# QCLogic_Rev_A_Sht3_GPS.net
KiCad netlist of a schematic drawn in Altium Designer
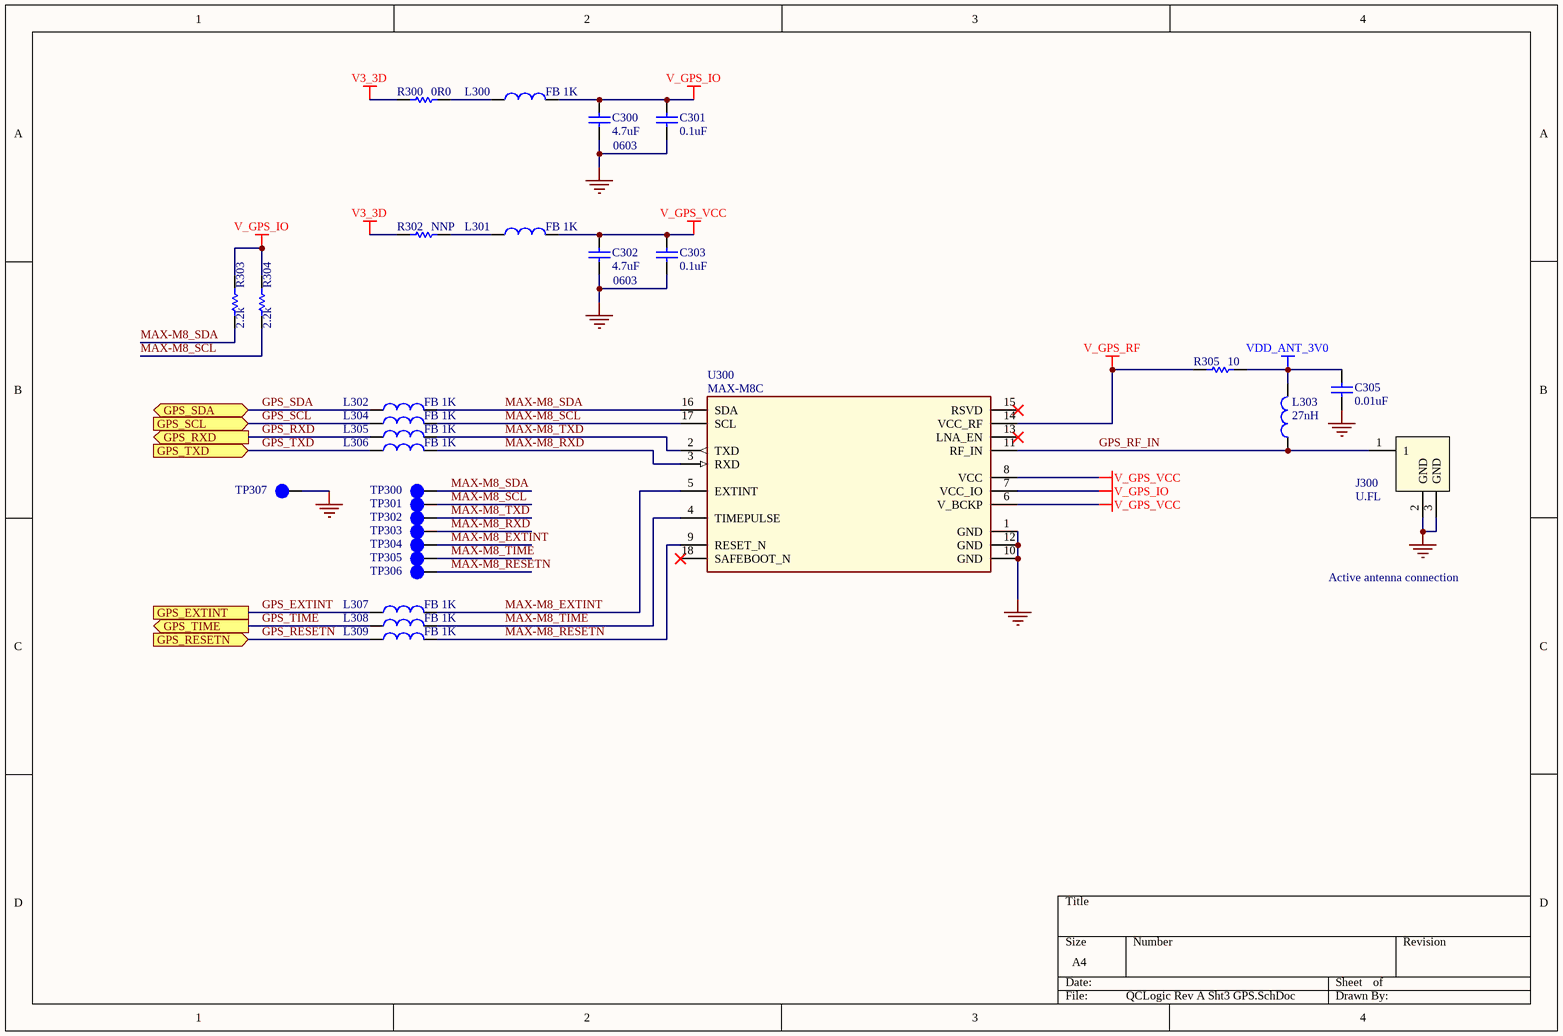
[diagram p0: QCLogic Rev A Sht3 GPS.SchDoc]

(export (version "E")
  (design (tool "Eeschema 10.0.6"))
  (components
    (comp (ref "C300")
      (value "4.7uF")
      (footprint "SMD CAP 0603")
      (description "CAP CER 4.7UF 16V X7S 0603")
      (fields
        (field (name "2. MANUFACTURER PART NUMBER") "GRM188C71C475KE21D")
        (field (name "4. PACKAGE") "0603")
      )
      (libsource (lib "SBCLib") (part "CAP MLCC SMD"))
    )
    (comp (ref "C301")
      (value "0.1uF")
      (footprint "SMD CAP 0402")
      (description "CAP CER 0.1UF 25V X7R 0402")
      (fields (field (name "2. MANUFACTURER PART NUMBER") "CC0402KRX7R8BB104"))
      (libsource (lib "SBCLib") (part "CAP MLCC SMD"))
    )
    (comp (ref "C302")
      (value "4.7uF")
      (footprint "SMD CAP 0603")
      (description "CAP CER 4.7UF 16V X7S 0603")
      (fields
        (field (name "2. MANUFACTURER PART NUMBER") "GRM188C71C475KE21D")
        (field (name "4. PACKAGE") "0603")
      )
      (libsource (lib "SBCLib") (part "CAP MLCC SMD"))
    )
    (comp (ref "C303")
      (value "0.1uF")
      (footprint "SMD CAP 0402")
      (description "CAP CER 0.1UF 25V X7R 0402")
      (fields (field (name "2. MANUFACTURER PART NUMBER") "CC0402KRX7R8BB104"))
      (libsource (lib "SBCLib") (part "CAP MLCC SMD"))
    )
    (comp (ref "C305")
      (value "0.01uF")
      (footprint "SMD CAP 0402")
      (description "CAP CER 10000PF 16V X7R 0402")
      (fields (field (name "2. MANUFACTURER PART NUMBER") "0402B103K160CT"))
      (libsource (lib "SBCLib") (part "CAP MLCC SMD"))
    )
    (comp (ref "J300")
      (value "U.FL")
      (footprint "U.FL")
      (description "CONN UMCC MICRO-COAX RECEPTACLE, GEN")
      (fields (field (name "2. MANUFACTURER PART NUMBER") "2337019-1"))
      (libsource (lib "SBCLib") (part "CONN UMCC MICRO-COAX RECEPTACLE, GEN"))
    )
    (comp (ref "L300")
      (value "FB 1K")
      (footprint "SMD RES 0402")
      (description "FERRITE BEAD 1 KOHM 0402 1LN")
      (fields (field (name "2. MANUFACTURER PART NUMBER") "BLM15HD102SN1D"))
      (libsource (lib "SBCLib") (part "INDUCTOR"))
    )
    (comp (ref "L301")
      (value "FB 1K")
      (footprint "SMD RES 0402")
      (description "FERRITE BEAD 1 KOHM 0402 1LN")
      (fields (field (name "2. MANUFACTURER PART NUMBER") "BLM15HD102SN1D"))
      (libsource (lib "SBCLib") (part "INDUCTOR"))
    )
    (comp (ref "L302")
      (value "FB 1K")
      (footprint "SMD RES 0402")
      (description "FERRITE BEAD 1 KOHM 0402 1LN")
      (fields (field (name "2. MANUFACTURER PART NUMBER") "BLM15HD102SN1D"))
      (libsource (lib "SBCLib") (part "INDUCTOR"))
    )
    (comp (ref "L303")
      (value "27nH")
      (footprint "SMD RES 0402")
      (description "IND 27NH 350MA 460 MOHM")
      (fields (field (name "2. MANUFACTURER PART NUMBER") "LQG15HS27NJ02D"))
      (libsource (lib "SBCLib") (part "INDUCTOR"))
    )
    (comp (ref "L304")
      (value "FB 1K")
      (footprint "SMD RES 0402")
      (description "FERRITE BEAD 1 KOHM 0402 1LN")
      (fields (field (name "2. MANUFACTURER PART NUMBER") "BLM15HD102SN1D"))
      (libsource (lib "SBCLib") (part "INDUCTOR"))
    )
    (comp (ref "L305")
      (value "FB 1K")
      (footprint "SMD RES 0402")
      (description "FERRITE BEAD 1 KOHM 0402 1LN")
      (fields (field (name "2. MANUFACTURER PART NUMBER") "BLM15HD102SN1D"))
      (libsource (lib "SBCLib") (part "INDUCTOR"))
    )
    (comp (ref "L306")
      (value "FB 1K")
      (footprint "SMD RES 0402")
      (description "FERRITE BEAD 1 KOHM 0402 1LN")
      (fields (field (name "2. MANUFACTURER PART NUMBER") "BLM15HD102SN1D"))
      (libsource (lib "SBCLib") (part "INDUCTOR"))
    )
    (comp (ref "L307")
      (value "FB 1K")
      (footprint "SMD RES 0402")
      (description "FERRITE BEAD 1 KOHM 0402 1LN")
      (fields (field (name "2. MANUFACTURER PART NUMBER") "BLM15HD102SN1D"))
      (libsource (lib "SBCLib") (part "INDUCTOR"))
    )
    (comp (ref "L308")
      (value "FB 1K")
      (footprint "SMD RES 0402")
      (description "FERRITE BEAD 1 KOHM 0402 1LN")
      (fields (field (name "2. MANUFACTURER PART NUMBER") "BLM15HD102SN1D"))
      (libsource (lib "SBCLib") (part "INDUCTOR"))
    )
    (comp (ref "L309")
      (value "FB 1K")
      (footprint "SMD RES 0402")
      (description "FERRITE BEAD 1 KOHM 0402 1LN")
      (fields (field (name "2. MANUFACTURER PART NUMBER") "BLM15HD102SN1D"))
      (libsource (lib "SBCLib") (part "INDUCTOR"))
    )
    (comp (ref "R300")
      (value "0R0")
      (footprint "SMD RES 0402")
      (description "RES SMD 0 OHM JUMPER 1/16W 0402")
      (fields (field (name "2. MANUFACTURER PART NUMBER") "RC0402FR-070RL"))
      (libsource (lib "SBCLib") (part "RES SMD"))
    )
    (comp (ref "R302")
      (value "NNP")
      (footprint "SMD RES 0402")
      (description "RES SMD 0 OHM JUMPER 1/16W 0402")
      (fields (field (name "2. MANUFACTURER PART NUMBER") "RC0402FR-070RL"))
      (libsource (lib "SBCLib") (part "RES SMD"))
    )
    (comp (ref "R303")
      (value "2.2k")
      (footprint "SMD RES 0402")
      (description "RES SMD 2.2K OHM 1% 1/16W 0402")
      (fields (field (name "2. MANUFACTURER PART NUMBER") "RC0402FR-072K2L"))
      (libsource (lib "SBCLib") (part "RES SMD"))
    )
    (comp (ref "R304")
      (value "2.2k")
      (footprint "SMD RES 0402")
      (description "RES SMD 2.2K OHM 1% 1/16W 0402")
      (fields (field (name "2. MANUFACTURER PART NUMBER") "RC0402FR-072K2L"))
      (libsource (lib "SBCLib") (part "RES SMD"))
    )
    (comp (ref "R305")
      (value "10")
      (footprint "SMD RES 0402")
      (description "RES SMD 10 OHM 5% 1/16W 0402")
      (fields (field (name "2. MANUFACTURER PART NUMBER") "RC0402JR-0710RL"))
      (libsource (lib "SBCLib") (part "RES SMD"))
    )
    (comp (ref "TP300")
      (value "TESTPOINT SMD")
      (footprint "TESTPOINT 0.5mm DIA")
      (description "TESTPOINT SMD PAD")
      (libsource (lib "SBCLib") (part "TESTPOINT PAD"))
    )
    (comp (ref "TP301")
      (value "TESTPOINT SMD")
      (footprint "TESTPOINT 0.5mm DIA")
      (description "TESTPOINT SMD PAD")
      (libsource (lib "SBCLib") (part "TESTPOINT PAD"))
    )
    (comp (ref "TP302")
      (value "TESTPOINT SMD")
      (footprint "TESTPOINT 0.5mm DIA")
      (description "TESTPOINT SMD PAD")
      (libsource (lib "SBCLib") (part "TESTPOINT PAD"))
    )
    (comp (ref "TP303")
      (value "TESTPOINT SMD")
      (footprint "TESTPOINT 0.5mm DIA")
      (description "TESTPOINT SMD PAD")
      (libsource (lib "SBCLib") (part "TESTPOINT PAD"))
    )
    (comp (ref "TP304")
      (value "TESTPOINT SMD")
      (footprint "TESTPOINT 0.5mm DIA")
      (description "TESTPOINT SMD PAD")
      (libsource (lib "SBCLib") (part "TESTPOINT PAD"))
    )
    (comp (ref "TP305")
      (value "TESTPOINT SMD")
      (footprint "TESTPOINT 0.5mm DIA")
      (description "TESTPOINT SMD PAD")
      (libsource (lib "SBCLib") (part "TESTPOINT PAD"))
    )
    (comp (ref "TP306")
      (value "TESTPOINT SMD")
      (footprint "TESTPOINT 0.5mm DIA")
      (description "TESTPOINT SMD PAD")
      (libsource (lib "SBCLib") (part "TESTPOINT PAD"))
    )
    (comp (ref "TP307")
      (value "TESTPOINT SMD")
      (footprint "TESTPOINT 1mm DIA")
      (description "TESTPOINT SMD PAD")
      (libsource (lib "SBCLib") (part "TESTPOINT PAD"))
    )
    (comp (ref "U300")
      (value "MAX-M8C")
      (footprint "MAX-M8")
      (description "MODULE RF RCVR GNSS/GPS 1.575GHZ 18LCC")
      (fields (field (name "2. MANUFACTURER PART NUMBER") "MAX-M8C-0"))
      (libsource (lib "SBCLib") (part "MODULE RF RCVR GNSS/GPS 1.575GHZ 18LCC"))
    )
  )
  (nets
    (net (code "1") (name "/GPS_EXTINT") (class "Default")
      (node (ref "L307") (pin "1") (pinfunction "1_1") (pintype "passive"))
    )
    (net (code "2") (name "/GPS_RESETN") (class "Default")
      (node (ref "L309") (pin "1") (pinfunction "1_1") (pintype "passive"))
    )
    (net (code "3") (name "/GPS_RF_IN") (class "Default")
      (node (ref "J300") (pin "1") (pinfunction "1_1") (pintype "passive"))
      (node (ref "L303") (pin "1") (pinfunction "1_1") (pintype "passive"))
      (node (ref "U300") (pin "11") (pinfunction "RF_IN_11") (pintype "passive"))
    )
    (net (code "4") (name "/GPS_RXD") (class "Default")
      (node (ref "L305") (pin "1") (pinfunction "1_1") (pintype "passive"))
    )
    (net (code "5") (name "/GPS_SCL") (class "Default")
      (node (ref "L304") (pin "1") (pinfunction "1_1") (pintype "passive"))
    )
    (net (code "6") (name "/GPS_SDA") (class "Default")
      (node (ref "L302") (pin "1") (pinfunction "1_1") (pintype "passive"))
    )
    (net (code "7") (name "/GPS_TIME") (class "Default")
      (node (ref "L308") (pin "1") (pinfunction "1_1") (pintype "passive"))
    )
    (net (code "8") (name "/GPS_TXD") (class "Default")
      (node (ref "L306") (pin "1") (pinfunction "1_1") (pintype "passive"))
    )
    (net (code "9") (name "/MAX-M8_EXTINT") (class "Default")
      (node (ref "L307") (pin "2") (pinfunction "2_2") (pintype "passive"))
      (node (ref "TP304") (pin "1") (pinfunction "1_1") (pintype "passive"))
      (node (ref "U300") (pin "5") (pinfunction "EXTINT_5") (pintype "passive"))
    )
    (net (code "10") (name "/MAX-M8_RESETN") (class "Default")
      (node (ref "L309") (pin "2") (pinfunction "2_2") (pintype "passive"))
      (node (ref "TP306") (pin "1") (pinfunction "1_1") (pintype "passive"))
      (node (ref "U300") (pin "9") (pinfunction "RESET_N_9") (pintype "passive"))
    )
    (net (code "11") (name "/MAX-M8_RXD") (class "Default")
      (node (ref "L306") (pin "2") (pinfunction "2_2") (pintype "passive"))
      (node (ref "TP303") (pin "1") (pinfunction "1_1") (pintype "passive"))
      (node (ref "U300") (pin "3") (pinfunction "RXD_3") (pintype "input"))
    )
    (net (code "12") (name "/MAX-M8_SCL") (class "Default")
      (node (ref "L304") (pin "2") (pinfunction "2_2") (pintype "passive"))
      (node (ref "R304") (pin "2") (pinfunction "2_2") (pintype "passive"))
      (node (ref "TP301") (pin "1") (pinfunction "1_1") (pintype "passive"))
      (node (ref "U300") (pin "17") (pinfunction "SCL_17") (pintype "passive"))
    )
    (net (code "13") (name "/MAX-M8_SDA") (class "Default")
      (node (ref "L302") (pin "2") (pinfunction "2_2") (pintype "passive"))
      (node (ref "R303") (pin "2") (pinfunction "2_2") (pintype "passive"))
      (node (ref "TP300") (pin "1") (pinfunction "1_1") (pintype "passive"))
      (node (ref "U300") (pin "16") (pinfunction "SDA_16") (pintype "passive"))
    )
    (net (code "14") (name "/MAX-M8_TIME") (class "Default")
      (node (ref "L308") (pin "2") (pinfunction "2_2") (pintype "passive"))
      (node (ref "TP305") (pin "1") (pinfunction "1_1") (pintype "passive"))
      (node (ref "U300") (pin "4") (pinfunction "TIMEPULSE_4") (pintype "passive"))
    )
    (net (code "15") (name "/MAX-M8_TXD") (class "Default")
      (node (ref "L305") (pin "2") (pinfunction "2_2") (pintype "passive"))
      (node (ref "TP302") (pin "1") (pinfunction "1_1") (pintype "passive"))
      (node (ref "U300") (pin "2") (pinfunction "TXD_2") (pintype "output"))
    )
    (net (code "16") (name "GND") (class "Default")
      (node (ref "C300") (pin "2") (pinfunction "2_2") (pintype "passive"))
      (node (ref "C301") (pin "1") (pinfunction "1_1") (pintype "passive"))
      (node (ref "C302") (pin "2") (pinfunction "2_2") (pintype "passive"))
      (node (ref "C303") (pin "1") (pinfunction "1_1") (pintype "passive"))
      (node (ref "C305") (pin "2") (pinfunction "2_2") (pintype "passive"))
      (node (ref "J300") (pin "2") (pinfunction "GND_2") (pintype "passive"))
      (node (ref "J300") (pin "3") (pinfunction "GND_3") (pintype "passive"))
      (node (ref "TP307") (pin "1") (pinfunction "1_1") (pintype "passive"))
      (node (ref "U300") (pin "1") (pinfunction "GND_1") (pintype "passive"))
      (node (ref "U300") (pin "10") (pinfunction "GND_10") (pintype "passive"))
      (node (ref "U300") (pin "12") (pinfunction "GND_12") (pintype "passive"))
    )
    (net (code "17") (name "Net-(L300-Pad1)") (class "Default")
      (node (ref "L300") (pin "1") (pinfunction "1_1") (pintype "passive"))
      (node (ref "R300") (pin "2") (pinfunction "2_2") (pintype "passive"))
    )
    (net (code "18") (name "Net-(L301-Pad1)") (class "Default")
      (node (ref "L301") (pin "1") (pinfunction "1_1") (pintype "passive"))
      (node (ref "R302") (pin "2") (pinfunction "2_2") (pintype "passive"))
    )
    (net (code "19") (name "V3_3D") (class "Default")
      (node (ref "R300") (pin "1") (pinfunction "1_1") (pintype "passive"))
      (node (ref "R302") (pin "1") (pinfunction "1_1") (pintype "passive"))
    )
    (net (code "20") (name "VDD_ANT_3V0") (class "Default")
      (node (ref "C305") (pin "1") (pinfunction "1_1") (pintype "passive"))
      (node (ref "L303") (pin "2") (pinfunction "2_2") (pintype "passive"))
      (node (ref "R305") (pin "2") (pinfunction "2_2") (pintype "passive"))
    )
    (net (code "21") (name "V_GPS_IO") (class "Default")
      (node (ref "C300") (pin "1") (pinfunction "1_1") (pintype "passive"))
      (node (ref "C301") (pin "2") (pinfunction "2_2") (pintype "passive"))
      (node (ref "L300") (pin "2") (pinfunction "2_2") (pintype "passive"))
      (node (ref "R303") (pin "1") (pinfunction "1_1") (pintype "passive"))
      (node (ref "R304") (pin "1") (pinfunction "1_1") (pintype "passive"))
      (node (ref "U300") (pin "7") (pinfunction "VCC_IO_7") (pintype "passive"))
    )
    (net (code "22") (name "V_GPS_RF") (class "Default")
      (node (ref "R305") (pin "1") (pinfunction "1_1") (pintype "passive"))
      (node (ref "U300") (pin "14") (pinfunction "VCC_RF_14") (pintype "passive"))
    )
    (net (code "23") (name "V_GPS_VCC") (class "Default")
      (node (ref "C302") (pin "1") (pinfunction "1_1") (pintype "passive"))
      (node (ref "C303") (pin "2") (pinfunction "2_2") (pintype "passive"))
      (node (ref "L301") (pin "2") (pinfunction "2_2") (pintype "passive"))
      (node (ref "U300") (pin "6") (pinfunction "V_BCKP_6") (pintype "passive"))
      (node (ref "U300") (pin "8") (pinfunction "VCC_8") (pintype "passive"))
    )
    (net (code "24") (name "unconnected-(U300-LNA_EN-Pad13)") (class "Default")
      (node (ref "U300") (pin "13") (pinfunction "LNA_EN_13") (pintype "passive+no_connect"))
    )
    (net (code "25") (name "unconnected-(U300-RSVD-Pad15)") (class "Default")
      (node (ref "U300") (pin "15") (pinfunction "RSVD_15") (pintype "passive+no_connect"))
    )
    (net (code "26") (name "unconnected-(U300-SAFEBOOT_N-Pad18)") (class "Default")
      (node (ref "U300") (pin "18") (pinfunction "SAFEBOOT_N_18") (pintype "passive+no_connect"))
    )
  )
)
